# WLED_MINI_v0_91.net
KiCad netlist of a schematic drawn in EAGLE
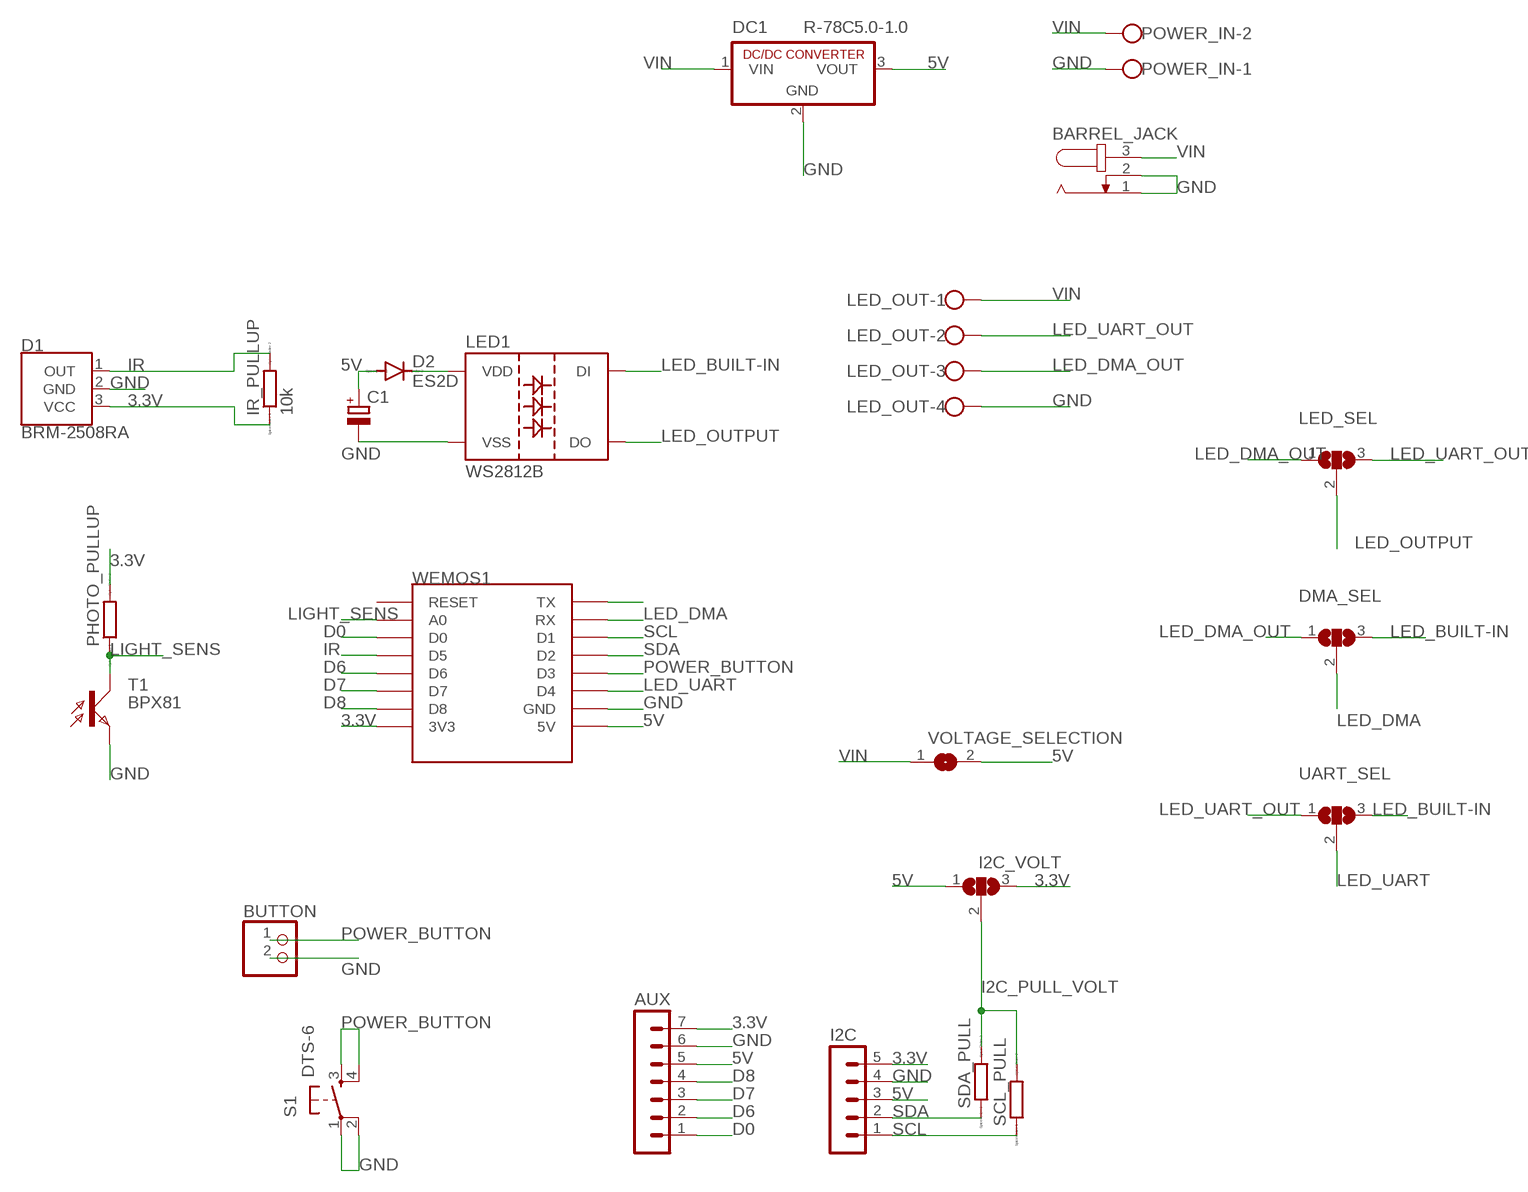
[diagram p0: schematic, sheet 1]

(export (version "E")
  (design (tool "Eeschema 10.0.6"))
  (components
    (comp (ref "AUX")
      (value "MA07-1")
      (footprint "eagle-import:MA07-1")
      (libsource (lib "eagle-import") (part "MA07-1"))
    )
    (comp (ref "BARREL_JACK")
      (value "JACK-PLUG0")
      (footprint "eagle-import:SPC4077")
      (libsource (lib "eagle-import") (part "JACK-PLUG0"))
    )
    (comp (ref "BUTTON")
      (value "PINHD-1X2")
      (footprint "eagle-import:1X02")
      (libsource (lib "eagle-import") (part "PINHD-1X2"))
    )
    (comp (ref "C1")
      (value "CPOL-EUE2.5-7")
      (footprint "eagle-import:E2,5-7")
      (libsource (lib "eagle-import") (part "CPOL-EUE2.5-7"))
    )
    (comp (ref "D1")
      (value "BRM-2508RA")
      (footprint "eagle-import:BRM-2508")
      (libsource (lib "eagle-import") (part "BRM-2508RA"))
    )
    (comp (ref "D2")
      (value "ES2D")
      (footprint "eagle-import:SMB")
      (libsource (lib "eagle-import") (part "ES2D"))
    )
    (comp (ref "DC1")
      (value "R-78C5.0-1.0")
      (footprint "eagle-import:SIP3")
      (libsource (lib "eagle-import") (part "R-78C-1.05.0"))
    )
    (comp (ref "DMA_SEL")
      (value "SJ2W")
      (footprint "eagle-import:SJ_2")
      (libsource (lib "eagle-import") (part "SJ2W"))
    )
    (comp (ref "I2C")
      (value "MA05-1")
      (footprint "eagle-import:MA05-1")
      (libsource (lib "eagle-import") (part "MA05-1"))
    )
    (comp (ref "I2C_VOLT")
      (value "SJ2W")
      (footprint "eagle-import:SJ_2")
      (libsource (lib "eagle-import") (part "SJ2W"))
    )
    (comp (ref "IR_PULLUP")
      (value "10k")
      (footprint "eagle-import:0204_7")
      (libsource (lib "eagle-import") (part "R0204/7"))
    )
    (comp (ref "LED1")
      (value "WS2812B")
      (footprint "eagle-import:WS2812B")
      (libsource (lib "eagle-import") (part "WS2812B"))
    )
    (comp (ref "LED_OUT")
      (value "W237-4")
      (footprint "eagle-import:W237-4")
      (libsource (lib "eagle-import") (part "W237-4"))
    )
    (comp (ref "LED_SEL")
      (value "SJ2W")
      (footprint "eagle-import:SJ_2")
      (libsource (lib "eagle-import") (part "SJ2W"))
    )
    (comp (ref "PHOTO_PULLUP")
      (value "R0204/7")
      (footprint "eagle-import:0204_7")
      (libsource (lib "eagle-import") (part "R0204/7"))
    )
    (comp (ref "POWER_IN")
      (value "W237-102")
      (footprint "eagle-import:W237-102")
      (fields (field (name "MPN") "237-102"))
      (libsource (lib "eagle-import") (part "W237-102"))
    )
    (comp (ref "S1")
      (value "DTS-6")
      (footprint "eagle-import:DTS-6")
      (libsource (lib "eagle-import") (part "DTS-6"))
    )
    (comp (ref "SCL_PULL")
      (value "R0204/7")
      (footprint "eagle-import:0204_7")
      (libsource (lib "eagle-import") (part "R0204/7"))
    )
    (comp (ref "SDA_PULL")
      (value "R0204/7")
      (footprint "eagle-import:0204_7")
      (libsource (lib "eagle-import") (part "R0204/7"))
    )
    (comp (ref "T1")
      (value "BPX81")
      (footprint "eagle-import:BPX81")
      (libsource (lib "eagle-import") (part "BPX81"))
    )
    (comp (ref "UART_SEL")
      (value "SJ2W")
      (footprint "eagle-import:SJ_2")
      (libsource (lib "eagle-import") (part "SJ2W"))
    )
    (comp (ref "VOLTAGE_SELECTION")
      (value "SJ")
      (footprint "eagle-import:SJ")
      (libsource (lib "eagle-import") (part "SJ"))
    )
    (comp (ref "WEMOS1")
      (value "WEMOS-D1-MINI")
      (footprint "eagle-import:WEMOS-D1-MINI")
      (libsource (lib "eagle-import") (part "WEMOS-D1-MINI"))
    )
  )
  (nets
    (net (code "1") (name "/3.3V") (class "Default")
      (node (ref "AUX") (pin "7") (pinfunction "7_7") (pintype "passive"))
      (node (ref "D1") (pin "3") (pinfunction "VCC_3") (pintype "bidirectional"))
      (node (ref "I2C") (pin "5") (pinfunction "5_5") (pintype "passive"))
      (node (ref "I2C_VOLT") (pin "3") (pinfunction "3_3") (pintype "passive"))
      (node (ref "IR_PULLUP") (pin "1") (pinfunction "1_1") (pintype "passive"))
      (node (ref "PHOTO_PULLUP") (pin "2") (pinfunction "2_2") (pintype "passive"))
      (node (ref "WEMOS1") (pin "3V3") (pinfunction "3V3_3V3") (pintype "bidirectional"))
    )
    (net (code "2") (name "/5V") (class "Default")
      (node (ref "AUX") (pin "5") (pinfunction "5_5") (pintype "passive"))
      (node (ref "C1") (pin "+") (pinfunction "+_+") (pintype "passive"))
      (node (ref "D2") (pin "A") (pinfunction "A_A") (pintype "passive"))
      (node (ref "DC1") (pin "3") (pinfunction "VOUT_3") (pintype "passive"))
      (node (ref "I2C") (pin "3") (pinfunction "3_3") (pintype "passive"))
      (node (ref "I2C_VOLT") (pin "1") (pinfunction "1_1") (pintype "passive"))
      (node (ref "VOLTAGE_SELECTION") (pin "2") (pinfunction "2_2") (pintype "passive"))
      (node (ref "WEMOS1") (pin "5V") (pinfunction "5V_5V") (pintype "bidirectional"))
    )
    (net (code "3") (name "/D0") (class "Default")
      (node (ref "AUX") (pin "1") (pinfunction "1_1") (pintype "passive"))
      (node (ref "WEMOS1") (pin "D0") (pinfunction "D0_D0") (pintype "bidirectional"))
    )
    (net (code "4") (name "/D6") (class "Default")
      (node (ref "AUX") (pin "2") (pinfunction "2_2") (pintype "passive"))
      (node (ref "WEMOS1") (pin "D6") (pinfunction "D6_D6") (pintype "bidirectional"))
    )
    (net (code "5") (name "/D7") (class "Default")
      (node (ref "AUX") (pin "3") (pinfunction "3_3") (pintype "passive"))
      (node (ref "WEMOS1") (pin "D7") (pinfunction "D7_D7") (pintype "bidirectional"))
    )
    (net (code "6") (name "/D8") (class "Default")
      (node (ref "AUX") (pin "4") (pinfunction "4_4") (pintype "passive"))
      (node (ref "WEMOS1") (pin "D8") (pinfunction "D8_D8") (pintype "bidirectional"))
    )
    (net (code "7") (name "/GND") (class "Default")
      (node (ref "AUX") (pin "6") (pinfunction "6_6") (pintype "passive"))
      (node (ref "BARREL_JACK") (pin "1") (pinfunction "1_1") (pintype "passive"))
      (node (ref "BARREL_JACK") (pin "2") (pinfunction "2_2") (pintype "passive"))
      (node (ref "BUTTON") (pin "2") (pinfunction "2_2") (pintype "passive"))
      (node (ref "C1") (pin "-") (pinfunction "-_-") (pintype "passive"))
      (node (ref "D1") (pin "2") (pinfunction "GND_2") (pintype "bidirectional"))
      (node (ref "DC1") (pin "2") (pinfunction "GND_2") (pintype "passive"))
      (node (ref "I2C") (pin "4") (pinfunction "4_4") (pintype "passive"))
      (node (ref "LED1") (pin "3") (pinfunction "VSS_3") (pintype "bidirectional"))
      (node (ref "LED_OUT") (pin "4") (pinfunction "KL_4") (pintype "passive"))
      (node (ref "POWER_IN") (pin "1") (pinfunction "KL_1") (pintype "passive"))
      (node (ref "S1") (pin "1") (pinfunction "1_1") (pintype "passive"))
      (node (ref "S1") (pin "2") (pinfunction "2_2") (pintype "passive"))
      (node (ref "T1") (pin "E") (pinfunction "E_E") (pintype "passive"))
      (node (ref "WEMOS1") (pin "GND") (pinfunction "GND_GND") (pintype "bidirectional"))
    )
    (net (code "8") (name "/I2C_PULL_VOLT") (class "Default")
      (node (ref "I2C_VOLT") (pin "2") (pinfunction "2_2") (pintype "passive"))
      (node (ref "SCL_PULL") (pin "2") (pinfunction "2_2") (pintype "passive"))
      (node (ref "SDA_PULL") (pin "2") (pinfunction "2_2") (pintype "passive"))
    )
    (net (code "9") (name "/IR") (class "Default")
      (node (ref "D1") (pin "1") (pinfunction "OUT_1") (pintype "bidirectional"))
      (node (ref "IR_PULLUP") (pin "2") (pinfunction "2_2") (pintype "passive"))
      (node (ref "WEMOS1") (pin "D5") (pinfunction "D5_D5") (pintype "bidirectional"))
    )
    (net (code "10") (name "/LED_BUILT-IN") (class "Default")
      (node (ref "DMA_SEL") (pin "3") (pinfunction "3_3") (pintype "passive"))
      (node (ref "LED1") (pin "4") (pinfunction "DI_4") (pintype "bidirectional"))
      (node (ref "UART_SEL") (pin "3") (pinfunction "3_3") (pintype "passive"))
    )
    (net (code "11") (name "/LED_DMA") (class "Default")
      (node (ref "DMA_SEL") (pin "2") (pinfunction "2_2") (pintype "passive"))
      (node (ref "WEMOS1") (pin "RX") (pinfunction "RX_RX") (pintype "bidirectional"))
    )
    (net (code "12") (name "/LED_DMA_OUT") (class "Default")
      (node (ref "DMA_SEL") (pin "1") (pinfunction "1_1") (pintype "passive"))
      (node (ref "LED_OUT") (pin "3") (pinfunction "KL_3") (pintype "passive"))
      (node (ref "LED_SEL") (pin "1") (pinfunction "1_1") (pintype "passive"))
    )
    (net (code "13") (name "/LED_OUTPUT") (class "Default")
      (node (ref "LED1") (pin "2") (pinfunction "DO_2") (pintype "bidirectional"))
      (node (ref "LED_SEL") (pin "2") (pinfunction "2_2") (pintype "passive"))
    )
    (net (code "14") (name "/LED_UART") (class "Default")
      (node (ref "UART_SEL") (pin "2") (pinfunction "2_2") (pintype "passive"))
      (node (ref "WEMOS1") (pin "D4") (pinfunction "D4_D4") (pintype "bidirectional"))
    )
    (net (code "15") (name "/LED_UART_OUT") (class "Default")
      (node (ref "LED_OUT") (pin "2") (pinfunction "KL_2") (pintype "passive"))
      (node (ref "LED_SEL") (pin "3") (pinfunction "3_3") (pintype "passive"))
      (node (ref "UART_SEL") (pin "1") (pinfunction "1_1") (pintype "passive"))
    )
    (net (code "16") (name "/LIGHT_SENS") (class "Default")
      (node (ref "PHOTO_PULLUP") (pin "1") (pinfunction "1_1") (pintype "passive"))
      (node (ref "T1") (pin "C") (pinfunction "C_C") (pintype "passive"))
      (node (ref "WEMOS1") (pin "A0") (pinfunction "A0_A0") (pintype "bidirectional"))
    )
    (net (code "17") (name "/POWER_BUTTON") (class "Default")
      (node (ref "BUTTON") (pin "1") (pinfunction "1_1") (pintype "passive"))
      (node (ref "S1") (pin "3") (pinfunction "3_3") (pintype "passive"))
      (node (ref "S1") (pin "4") (pinfunction "4_4") (pintype "passive"))
      (node (ref "WEMOS1") (pin "D3") (pinfunction "D3_D3") (pintype "bidirectional"))
    )
    (net (code "18") (name "/SCL") (class "Default")
      (node (ref "I2C") (pin "1") (pinfunction "1_1") (pintype "passive"))
      (node (ref "SCL_PULL") (pin "1") (pinfunction "1_1") (pintype "passive"))
      (node (ref "WEMOS1") (pin "D1") (pinfunction "D1_D1") (pintype "bidirectional"))
    )
    (net (code "19") (name "/SDA") (class "Default")
      (node (ref "I2C") (pin "2") (pinfunction "2_2") (pintype "passive"))
      (node (ref "SDA_PULL") (pin "1") (pinfunction "1_1") (pintype "passive"))
      (node (ref "WEMOS1") (pin "D2") (pinfunction "D2_D2") (pintype "bidirectional"))
    )
    (net (code "20") (name "/VIN") (class "Default")
      (node (ref "BARREL_JACK") (pin "3") (pinfunction "3_3") (pintype "passive"))
      (node (ref "DC1") (pin "1") (pinfunction "VIN_1") (pintype "passive"))
      (node (ref "LED_OUT") (pin "1") (pinfunction "KL_1") (pintype "passive"))
      (node (ref "POWER_IN") (pin "2") (pinfunction "KL_2") (pintype "passive"))
      (node (ref "VOLTAGE_SELECTION") (pin "1") (pinfunction "1_1") (pintype "passive"))
    )
    (net (code "21") (name "Net-(LED1-VDD)") (class "Default")
      (node (ref "D2") (pin "C") (pinfunction "C_C") (pintype "passive"))
      (node (ref "LED1") (pin "1") (pinfunction "VDD_1") (pintype "bidirectional"))
    )
    (net (code "22") (name "unconnected-(WEMOS1-PadRESET)") (class "Default")
      (node (ref "WEMOS1") (pin "RESET") (pinfunction "RESET_RESET") (pintype "bidirectional"))
    )
    (net (code "23") (name "unconnected-(WEMOS1-PadTX)") (class "Default")
      (node (ref "WEMOS1") (pin "TX") (pinfunction "TX_TX") (pintype "bidirectional"))
    )
  )
)
